# Medidor_bateria.net
KiCad netlist of a schematic drawn in Altium Designer
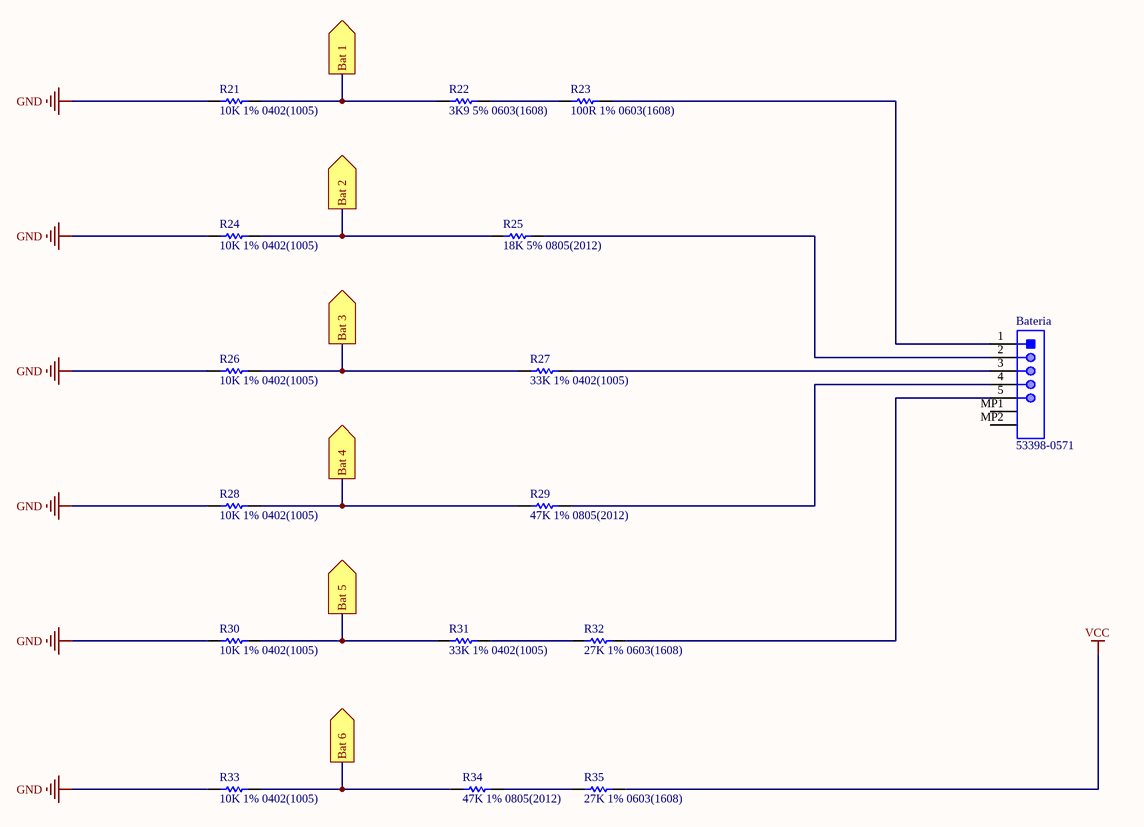
[diagram p0: Medidor bateria.SchDoc]

(export (version "E")
  (design (tool "Eeschema 10.0.6"))
  (components
    (comp (ref "Bateria")
      (value "53398-0571")
      (footprint "MOLX-53398-0571-5_V")
      (description "Male Header, Pitch 1.25 mm, 1 x 5 Postion, Height 4.7 mm, -40 to 85 degC, RoHS, Tape and Reel")
      (fields (field (name "MANUFACTURER") "Molex"))
      (libsource (lib "Moles_53398-0571") (part "CMP-2000-05250-1"))
    )
    (comp (ref "R21")
      (value "10K 1% 0402(1005)")
      (footprint "RESC0402(1005)_L")
      (description "10K 0.063W 1% 0402 (1005 Metric)  SMD                               71-CRCW040210K0FKEDC")
      (fields (field (name "TOLERANCE") "1 %") (field (name "POWER") "0.063 W"))
      (libsource (lib "Resistor 0402 10K") (part "CMP-1011-00623-1"))
    )
    (comp (ref "R22")
      (value "3K9 5% 0603(1608)")
      (footprint "RESC0603(1608)_L")
      (description "3K9 0.1W 5% 0603 (1608 Metric)  SMD                                 755-ESR03EZPJ392")
      (fields (field (name "POWER") "0.25 W") (field (name "TOLERANCE") "5 %"))
      (libsource (lib "Resistor 0603 3K9") (part "CMP-1012-00088-1"))
    )
    (comp (ref "R23")
      (value "100R 1% 0603(1608)")
      (footprint "RESC0603(1608)_L")
      (description "100R 0.1W 1% 0603 (1608 Metric)  SMD                               71-CRCW0603100RFKEAC")
      (fields (field (name "TOLERANCE") "1 %") (field (name "POWER") "0.1 W"))
      (libsource (lib "Resistor 0603 100Ohms") (part "CMP-1012-00397-1"))
    )
    (comp (ref "R24")
      (value "10K 1% 0402(1005)")
      (footprint "RESC0402(1005)_L")
      (description "10K 0.063W 1% 0402 (1005 Metric)  SMD                                  71-CRCW040210K0FKEDC")
      (fields (field (name "TOLERANCE") "1 %") (field (name "POWER") "0.063 W"))
      (libsource (lib "Resistor 0402 10K") (part "CMP-1011-00623-1"))
    )
    (comp (ref "R25")
      (value "18K 5% 0805(2012)")
      (footprint "RESC0805(2012)_N")
      (description "18K 0.125W 5% 0805 (2012 Metric)  SMD                                  667-ERJ-6GEYJ183V")
      (fields (field (name "POWER") "0.125 W") (field (name "TOLERANCE") "5 %"))
      (libsource (lib "Resistor 0805 18K") (part "CMP-1013-00104-1"))
    )
    (comp (ref "R26")
      (value "10K 1% 0402(1005)")
      (footprint "RESC0402(1005)_L")
      (description "10K 0.063W 1% 0402 (1005 Metric)  SMD                                 71-CRCW040210K0FKEDC")
      (fields (field (name "TOLERANCE") "1 %") (field (name "POWER") "0.063 W"))
      (libsource (lib "Resistor 0402 10K") (part "CMP-1011-00623-1"))
    )
    (comp (ref "R27")
      (value "33K 1% 0402(1005)")
      (footprint "RESC0402(1005)_L")
      (description "33K 0.063W 1% 0402 (1005 Metric)  SMD                                 755-SFR01MZPF3302")
      (fields (field (name "POWER") "0.063 W") (field (name "TOLERANCE") "1 %"))
      (libsource (lib "Resistor 0402 33K") (part "CMP-1011-00680-1"))
    )
    (comp (ref "R28")
      (value "10K 1% 0402(1005)")
      (footprint "RESC0402(1005)_L")
      (description "10K 0.063W 1% 0402 (1005 Metric)  SMD                                   71-CRCW040210K0FKEDC")
      (fields (field (name "TOLERANCE") "1 %") (field (name "POWER") "0.063 W"))
      (libsource (lib "Resistor 0402 10K") (part "CMP-1011-00623-1"))
    )
    (comp (ref "R29")
      (value "47K 1% 0805(2012)")
      (footprint "RESC0805(2012)_N")
      (description "47K 0.125W 1% 0805 (2012 Metric)  SMD                                66-PCFW0805LF034702B")
      (fields (field (name "POWER") "0.100 W") (field (name "TOLERANCE") "1 %"))
      (libsource (lib "Resistor 0805 47K") (part "CMP-1013-00699-1"))
    )
    (comp (ref "R30")
      (value "10K 1% 0402(1005)")
      (footprint "RESC0402(1005)_L")
      (description "10K 0.063W 1% 0402 (1005 Metric)  SMD                                         71-CRCW040210K0FKEDC")
      (fields (field (name "TOLERANCE") "1 %") (field (name "POWER") "0.063 W"))
      (libsource (lib "Resistor 0402 10K") (part "CMP-1011-00623-1"))
    )
    (comp (ref "R31")
      (value "33K 1% 0402(1005)")
      (footprint "RESC0402(1005)_L")
      (description "33K 0.063W 1% 0402 (1005 Metric)  SMD                                 755-SFR01MZPF3302")
      (fields (field (name "POWER") "0.063 W") (field (name "TOLERANCE") "1 %"))
      (libsource (lib "Resistor 0402 33K") (part "CMP-1011-00680-1"))
    )
    (comp (ref "R32")
      (value "27K 1% 0603(1608)")
      (footprint "RESC0603(1608)_L")
      (description "27K 0.1W 1% 0603 (1608 Metric)  SMD                                      755-ESR03EZPF2702")
      (fields (field (name "POWER") "0.250 W") (field (name "TOLERANCE") "1 %"))
      (libsource (lib "Resistor 0603 27K") (part "CMP-1012-00670-1"))
    )
    (comp (ref "R33")
      (value "10K 1% 0402(1005)")
      (footprint "RESC0402(1005)_L")
      (description "10K 0.063W 1% 0402 (1005 Metric)  SMD                                   71-CRCW040210K0FKEDC")
      (fields (field (name "TOLERANCE") "1 %") (field (name "POWER") "0.063 W"))
      (libsource (lib "Resistor 0402 10K") (part "CMP-1011-00623-1"))
    )
    (comp (ref "R34")
      (value "47K 1% 0805(2012)")
      (footprint "RESC0805(2012)_N")
      (description "47K 0.125W 1% 0805 (2012 Metric)  SMD                               66-PCFW0805LF034702B")
      (fields (field (name "POWER") "0.100 W") (field (name "TOLERANCE") "1 %"))
      (libsource (lib "Resistor 0805 47K") (part "CMP-1013-00699-1"))
    )
    (comp (ref "R35")
      (value "27K 1% 0603(1608)")
      (footprint "RESC0603(1608)_L")
      (description "27K 0.1W 1% 0603 (1608 Metric)  SMD                                          755-ESR03EZPF2702")
      (fields (field (name "POWER") "0.250 W") (field (name "TOLERANCE") "1 %"))
      (libsource (lib "Resistor 0603 27K") (part "CMP-1012-00670-1"))
    )
  )
  (nets
    (net (code "1") (name "/Bat 1") (class "Default")
      (node (ref "R21") (pin "2") (pinfunction "2_2") (pintype "passive"))
      (node (ref "R22") (pin "1") (pinfunction "1_1") (pintype "passive"))
    )
    (net (code "2") (name "/Bat 2") (class "Default")
      (node (ref "R24") (pin "2") (pinfunction "2_2") (pintype "passive"))
      (node (ref "R25") (pin "1") (pinfunction "1_1") (pintype "passive"))
    )
    (net (code "3") (name "/Bat 3") (class "Default")
      (node (ref "R26") (pin "2") (pinfunction "2_2") (pintype "passive"))
      (node (ref "R27") (pin "1") (pinfunction "1_1") (pintype "passive"))
    )
    (net (code "4") (name "/Bat 4") (class "Default")
      (node (ref "R28") (pin "2") (pinfunction "2_2") (pintype "passive"))
      (node (ref "R29") (pin "1") (pinfunction "1_1") (pintype "passive"))
    )
    (net (code "5") (name "/Bat 5") (class "Default")
      (node (ref "R30") (pin "2") (pinfunction "2_2") (pintype "passive"))
      (node (ref "R31") (pin "1") (pinfunction "1_1") (pintype "passive"))
    )
    (net (code "6") (name "/Bat 6") (class "Default")
      (node (ref "R33") (pin "2") (pinfunction "2_2") (pintype "passive"))
      (node (ref "R34") (pin "1") (pinfunction "1_1") (pintype "passive"))
    )
    (net (code "7") (name "GND") (class "Default")
      (node (ref "R21") (pin "1") (pinfunction "1_1") (pintype "passive"))
      (node (ref "R24") (pin "1") (pinfunction "1_1") (pintype "passive"))
      (node (ref "R26") (pin "1") (pinfunction "1_1") (pintype "passive"))
      (node (ref "R28") (pin "1") (pinfunction "1_1") (pintype "passive"))
      (node (ref "R30") (pin "1") (pinfunction "1_1") (pintype "passive"))
      (node (ref "R33") (pin "1") (pinfunction "1_1") (pintype "passive"))
    )
    (net (code "8") (name "Net-(Bateria-Pad1)") (class "Default")
      (node (ref "Bateria") (pin "1") (pinfunction "1_1") (pintype "passive"))
      (node (ref "R23") (pin "2") (pinfunction "2_2") (pintype "passive"))
    )
    (net (code "9") (name "Net-(Bateria-Pad2)") (class "Default")
      (node (ref "Bateria") (pin "2") (pinfunction "2_2") (pintype "passive"))
      (node (ref "R25") (pin "2") (pinfunction "2_2") (pintype "passive"))
    )
    (net (code "10") (name "Net-(Bateria-Pad3)") (class "Default")
      (node (ref "Bateria") (pin "3") (pinfunction "3_3") (pintype "passive"))
      (node (ref "R27") (pin "2") (pinfunction "2_2") (pintype "passive"))
    )
    (net (code "11") (name "Net-(Bateria-Pad4)") (class "Default")
      (node (ref "Bateria") (pin "4") (pinfunction "4_4") (pintype "passive"))
      (node (ref "R29") (pin "2") (pinfunction "2_2") (pintype "passive"))
    )
    (net (code "12") (name "Net-(Bateria-Pad5)") (class "Default")
      (node (ref "Bateria") (pin "5") (pinfunction "5_5") (pintype "passive"))
      (node (ref "R32") (pin "2") (pinfunction "2_2") (pintype "passive"))
    )
    (net (code "13") (name "Net-(R22-Pad2)") (class "Default")
      (node (ref "R22") (pin "2") (pinfunction "2_2") (pintype "passive"))
      (node (ref "R23") (pin "1") (pinfunction "1_1") (pintype "passive"))
    )
    (net (code "14") (name "Net-(R31-Pad2)") (class "Default")
      (node (ref "R31") (pin "2") (pinfunction "2_2") (pintype "passive"))
      (node (ref "R32") (pin "1") (pinfunction "1_1") (pintype "passive"))
    )
    (net (code "15") (name "Net-(R34-Pad2)") (class "Default")
      (node (ref "R34") (pin "2") (pinfunction "2_2") (pintype "passive"))
      (node (ref "R35") (pin "1") (pinfunction "1_1") (pintype "passive"))
    )
    (net (code "16") (name "VCC") (class "Default")
      (node (ref "R35") (pin "2") (pinfunction "2_2") (pintype "passive"))
    )
    (net (code "17") (name "unconnected-(Bateria-PadMP1)") (class "Default")
      (node (ref "Bateria") (pin "MP1") (pinfunction "MP1_MP1") (pintype "passive"))
    )
    (net (code "18") (name "unconnected-(Bateria-PadMP2)") (class "Default")
      (node (ref "Bateria") (pin "MP2") (pinfunction "MP2_MP2") (pintype "passive"))
    )
  )
)
